# MCP2515-2561_CAN_brekaout.net
KiCad netlist of a schematic drawn in EAGLE
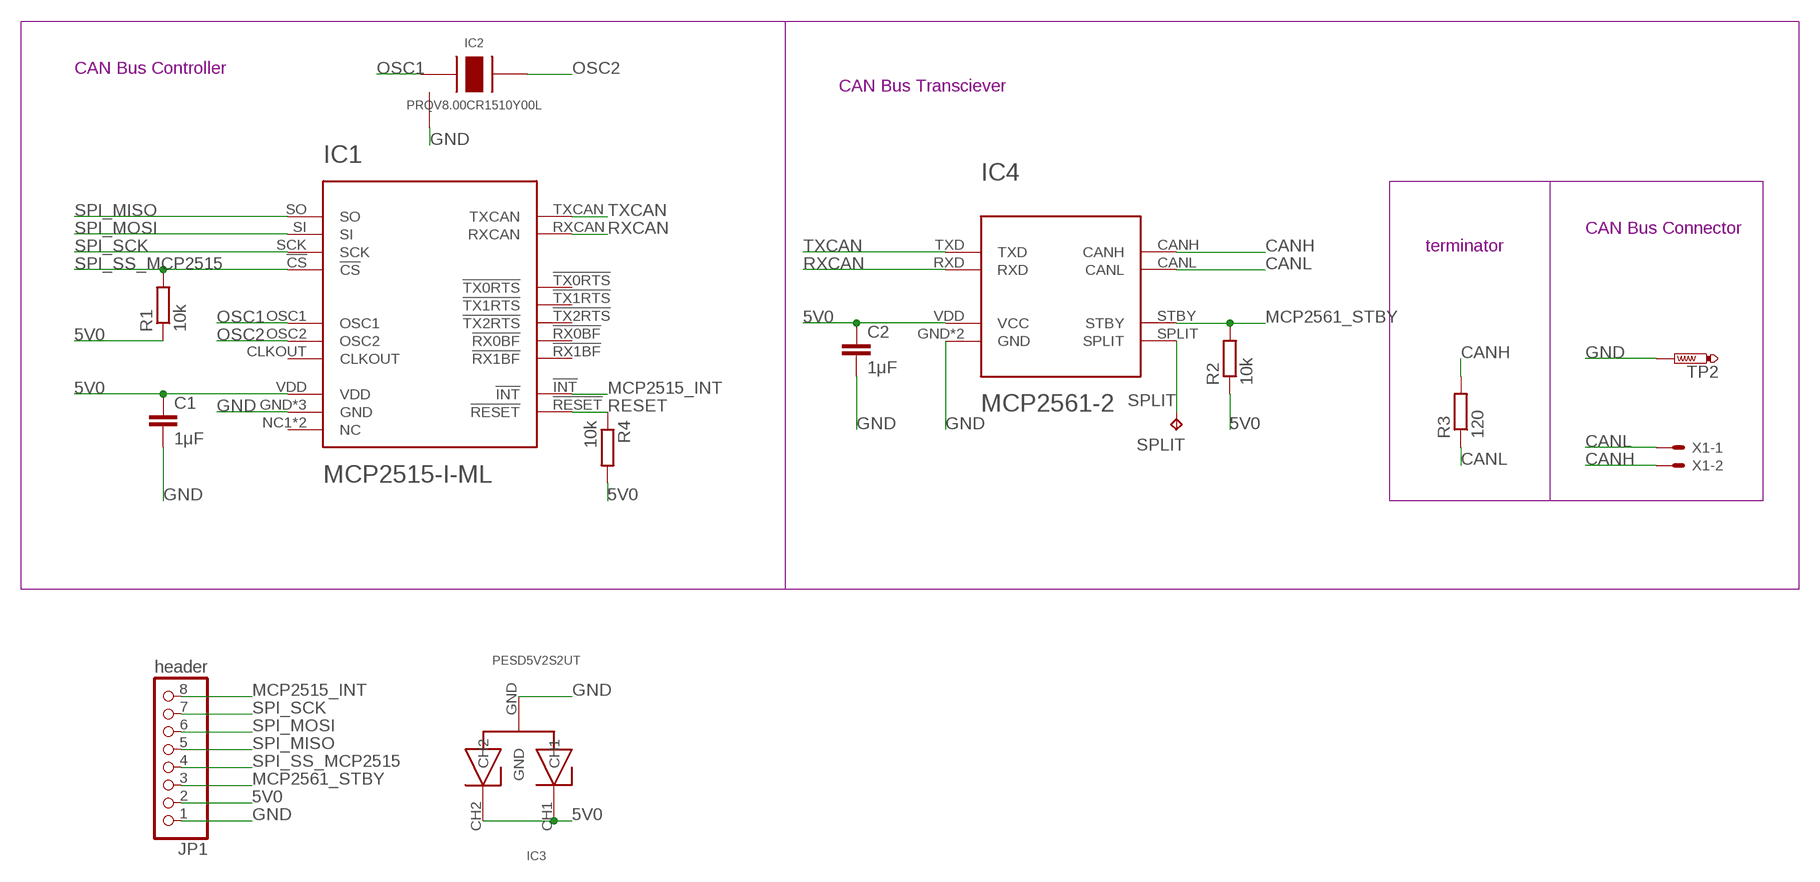
[diagram p0: schematic, sheet 1]

(export (version "E")
  (design (tool "Eeschema 10.0.6"))
  (components
    (comp (ref "C1")
      (value "1μF")
      (footprint "eagle-import:C0402")
      (libsource (lib "eagle-import") (part "C-EUC0402"))
    )
    (comp (ref "C2")
      (value "1μF")
      (footprint "eagle-import:C0402")
      (libsource (lib "eagle-import") (part "C-EUC0402"))
    )
    (comp (ref "IC1")
      (value "MCP2515-I-ML")
      (footprint "eagle-import:QFN20")
      (libsource (lib "eagle-import") (part "MCP2515-I-ML"))
    )
    (comp (ref "IC2")
      (value "PRQV8.00CR1510Y00L")
      (footprint "eagle-import:SMT")
      (libsource (lib "eagle-import") (part "PRQV"))
    )
    (comp (ref "IC3")
      (value "PESD5V2S2UT")
      (footprint "eagle-import:SOT-23")
      (libsource (lib "eagle-import") (part "PESDXS2UT"))
    )
    (comp (ref "IC4")
      (value "MCP2561-2")
      (footprint "eagle-import:DFN10")
      (libsource (lib "eagle-import") (part "MCP2561-2"))
    )
    (comp (ref "JP1")
      (value "header")
      (footprint "eagle-import:1X08")
      (libsource (lib "eagle-import") (part "PINHD-1X8"))
    )
    (comp (ref "R1")
      (value "10k")
      (footprint "eagle-import:R0402")
      (libsource (lib "eagle-import") (part "R-EU_R0402"))
    )
    (comp (ref "R2")
      (value "10k")
      (footprint "eagle-import:R0402")
      (libsource (lib "eagle-import") (part "R-EU_R0402"))
    )
    (comp (ref "R3")
      (value "120")
      (footprint "eagle-import:R0805")
      (libsource (lib "eagle-import") (part "R-EU_R0805"))
    )
    (comp (ref "R4")
      (value "10k")
      (footprint "eagle-import:R0402")
      (libsource (lib "eagle-import") (part "R-EU_R0402"))
    )
    (comp (ref "SPLIT")
      (value "TPB2,54")
      (footprint "eagle-import:B2,54")
      (libsource (lib "eagle-import") (part "TPB2,54"))
    )
    (comp (ref "TP2")
      (value "PTR1PAD1-13Y")
      (footprint "eagle-import:P1-13Y")
      (libsource (lib "eagle-import") (part "PTR1PAD1-13Y"))
    )
    (comp (ref "X1")
      (value "22-23-2021")
      (footprint "eagle-import:22-23-2021")
      (fields (field (name "MF") "MOLEX"))
      (libsource (lib "eagle-import") (part "22-23-2021"))
    )
  )
  (nets
    (net (code "1") (name "/5V0") (class "Default")
      (node (ref "C1") (pin "1") (pinfunction "1_1") (pintype "passive"))
      (node (ref "C2") (pin "1") (pinfunction "1_1") (pintype "passive"))
      (node (ref "IC1") (pin "VDD") (pinfunction "VDD_VDD") (pintype "power_in"))
      (node (ref "IC3") (pin "CH1") (pinfunction "CH1_CH1") (pintype "bidirectional"))
      (node (ref "IC3") (pin "CH2") (pinfunction "CH2_CH2") (pintype "bidirectional"))
      (node (ref "IC4") (pin "VDD") (pinfunction "VCC_VDD") (pintype "power_in"))
      (node (ref "JP1") (pin "2") (pinfunction "2_2") (pintype "passive"))
      (node (ref "R1") (pin "1") (pinfunction "1_1") (pintype "passive"))
      (node (ref "R2") (pin "1") (pinfunction "1_1") (pintype "passive"))
      (node (ref "R4") (pin "2") (pinfunction "2_2") (pintype "passive"))
    )
    (net (code "2") (name "/CANH") (class "Default")
      (node (ref "IC4") (pin "CANH") (pinfunction "CANH_CANH") (pintype "bidirectional"))
      (node (ref "R3") (pin "2") (pinfunction "2_2") (pintype "passive"))
      (node (ref "X1") (pin "2") (pinfunction "S_2") (pintype "passive"))
    )
    (net (code "3") (name "/CANL") (class "Default")
      (node (ref "IC4") (pin "CANL") (pinfunction "CANL_CANL") (pintype "bidirectional"))
      (node (ref "R3") (pin "1") (pinfunction "1_1") (pintype "passive"))
      (node (ref "X1") (pin "1") (pinfunction "S_1") (pintype "passive"))
    )
    (net (code "4") (name "/GND") (class "Default")
      (node (ref "C1") (pin "2") (pinfunction "2_2") (pintype "passive"))
      (node (ref "C2") (pin "2") (pinfunction "2_2") (pintype "passive"))
      (node (ref "IC1") (pin "GND") (pinfunction "GND_GND") (pintype "power_in"))
      (node (ref "IC1") (pin "GND1") (pinfunction "GND_GND1") (pintype "power_in"))
      (node (ref "IC1") (pin "GND6") (pinfunction "GND_GND6") (pintype "power_in"))
      (node (ref "IC2") (pin "GND") (pinfunction "GND_GND") (pintype "bidirectional"))
      (node (ref "IC3") (pin "GND") (pinfunction "GND_GND") (pintype "bidirectional"))
      (node (ref "IC4") (pin "GND") (pinfunction "GND_GND") (pintype "power_in"))
      (node (ref "IC4") (pin "VSS") (pinfunction "GND_VSS") (pintype "power_in"))
      (node (ref "JP1") (pin "1") (pinfunction "1_1") (pintype "passive"))
      (node (ref "TP2") (pin "TP") (pinfunction "TP_TP") (pintype "input"))
    )
    (net (code "5") (name "/MCP2515_INT") (class "Default")
      (node (ref "IC1") (pin "!INT!") (pinfunction "~{INT}_!INT!") (pintype "bidirectional"))
      (node (ref "JP1") (pin "8") (pinfunction "8_8") (pintype "passive"))
    )
    (net (code "6") (name "/MCP2561_STBY") (class "Default")
      (node (ref "IC4") (pin "STBY") (pinfunction "STBY_STBY") (pintype "bidirectional"))
      (node (ref "JP1") (pin "3") (pinfunction "3_3") (pintype "passive"))
      (node (ref "R2") (pin "2") (pinfunction "2_2") (pintype "passive"))
    )
    (net (code "7") (name "/OSC1") (class "Default")
      (node (ref "IC1") (pin "OSC1") (pinfunction "OSC1_OSC1") (pintype "bidirectional"))
      (node (ref "IC2") (pin "XTAL1") (pinfunction "XTAL1_XTAL1") (pintype "bidirectional"))
    )
    (net (code "8") (name "/OSC2") (class "Default")
      (node (ref "IC1") (pin "OSC2") (pinfunction "OSC2_OSC2") (pintype "bidirectional"))
      (node (ref "IC2") (pin "XTAL2") (pinfunction "XTAL2_XTAL2") (pintype "bidirectional"))
    )
    (net (code "9") (name "/RESET") (class "Default")
      (node (ref "IC1") (pin "!RESET!") (pinfunction "~{RESET}_!RESET!") (pintype "bidirectional"))
      (node (ref "R4") (pin "1") (pinfunction "1_1") (pintype "passive"))
    )
    (net (code "10") (name "/RXCAN") (class "Default")
      (node (ref "IC1") (pin "RXCAN") (pinfunction "RXCAN_RXCAN") (pintype "input"))
      (node (ref "IC4") (pin "RXD") (pinfunction "RXD_RXD") (pintype "output"))
    )
    (net (code "11") (name "/SPI_MISO") (class "Default")
      (node (ref "IC1") (pin "SO") (pinfunction "SO_SO") (pintype "output"))
      (node (ref "JP1") (pin "5") (pinfunction "5_5") (pintype "passive"))
    )
    (net (code "12") (name "/SPI_MOSI") (class "Default")
      (node (ref "IC1") (pin "SI") (pinfunction "SI_SI") (pintype "input"))
      (node (ref "JP1") (pin "6") (pinfunction "6_6") (pintype "passive"))
    )
    (net (code "13") (name "/SPI_SCK") (class "Default")
      (node (ref "IC1") (pin "SCK") (pinfunction "SCK_SCK") (pintype "bidirectional"))
      (node (ref "JP1") (pin "7") (pinfunction "7_7") (pintype "passive"))
    )
    (net (code "14") (name "/SPI_SS_MCP2515") (class "Default")
      (node (ref "IC1") (pin "!CS!") (pinfunction "~{CS}_!CS!") (pintype "bidirectional"))
      (node (ref "JP1") (pin "4") (pinfunction "4_4") (pintype "passive"))
      (node (ref "R1") (pin "2") (pinfunction "2_2") (pintype "passive"))
    )
    (net (code "15") (name "/SPLIT") (class "Default")
      (node (ref "IC4") (pin "SPLIT") (pinfunction "SPLIT_SPLIT") (pintype "bidirectional"))
      (node (ref "SPLIT") (pin "TP") (pinfunction "TP_TP") (pintype "input"))
    )
    (net (code "16") (name "/TXCAN") (class "Default")
      (node (ref "IC1") (pin "TXCAN") (pinfunction "TXCAN_TXCAN") (pintype "output"))
      (node (ref "IC4") (pin "TXD") (pinfunction "TXD_TXD") (pintype "input"))
    )
    (net (code "17") (name "unconnected-(IC1-NC-PadNC1)") (class "Default")
      (node (ref "IC1") (pin "NC1") (pinfunction "NC_NC1") (pintype "no_connect"))
    )
    (net (code "18") (name "unconnected-(IC1-NC-PadNC2)") (class "Default")
      (node (ref "IC1") (pin "NC2") (pinfunction "NC_NC2") (pintype "no_connect"))
    )
    (net (code "19") (name "unconnected-(IC1-PadCLKOUT)") (class "Default")
      (node (ref "IC1") (pin "CLKOUT") (pinfunction "CLKOUT_CLKOUT") (pintype "bidirectional"))
    )
    (net (code "20") (name "unconnected-(IC1-~{RX0BF}-Pad!RX0BF!)") (class "Default")
      (node (ref "IC1") (pin "!RX0BF!") (pinfunction "~{RX0BF}_!RX0BF!") (pintype "bidirectional"))
    )
    (net (code "21") (name "unconnected-(IC1-~{RX1BF}-Pad!RX1BF!)") (class "Default")
      (node (ref "IC1") (pin "!RX1BF!") (pinfunction "~{RX1BF}_!RX1BF!") (pintype "bidirectional"))
    )
    (net (code "22") (name "unconnected-(IC1-~{TX0RTS}-Pad!TX0RTS!)") (class "Default")
      (node (ref "IC1") (pin "!TX0RTS!") (pinfunction "~{TX0RTS}_!TX0RTS!") (pintype "bidirectional"))
    )
    (net (code "23") (name "unconnected-(IC1-~{TX1RTS}-Pad!TX1RTS!)") (class "Default")
      (node (ref "IC1") (pin "!TX1RTS!") (pinfunction "~{TX1RTS}_!TX1RTS!") (pintype "bidirectional"))
    )
    (net (code "24") (name "unconnected-(IC1-~{TX2RTS}-Pad!TX2RTS!)") (class "Default")
      (node (ref "IC1") (pin "!TX2RTS!") (pinfunction "~{TX2RTS}_!TX2RTS!") (pintype "bidirectional"))
    )
  )
)
